# LC_LPF12.net
KiCad netlist of a schematic drawn in Altium Designer
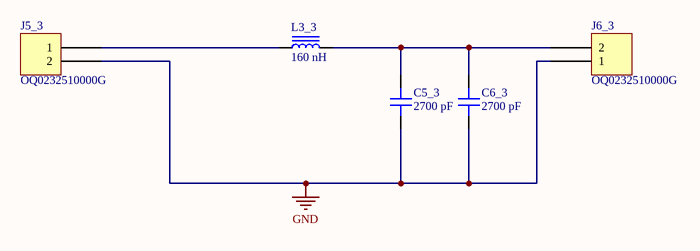
[diagram p0: LC_LPF12.SchDoc]

(export (version "E")
  (design (tool "Eeschema 10.0.6"))
  (components
    (comp (ref "C5_3")
      (value "2700 pF")
      (footprint "CAP 0603_1608")
      (description "CAP CER 2700PF 25V NP0 0603")
      (fields (field (name "PART NUMBER") "C0603C272F3GAC7867") (field (name "MANUFACTURER") "KEMET"))
      (libsource (lib "Celestial Altium Library - altium_library") (part "Capacitor"))
    )
    (comp (ref "C6_3")
      (value "2700 pF")
      (footprint "CAP 0603_1608")
      (description "CAP CER 2700PF 25V NP0 0603")
      (fields (field (name "PART NUMBER") "C0603C272F3GAC7867") (field (name "MANUFACTURER") "KEMET"))
      (libsource (lib "Celestial Altium Library - altium_library") (part "Capacitor"))
    )
    (comp (ref "J5_3")
      (value "OQ0232510000G")
      (footprint "FCI 06-381-2PIN")
      (description "TERM BLOCK HDR 2POS 90DEG 3.81MM")
      (fields (field (name "MANUFACTURER") "Amphenol Anytek"))
      (libsource (lib "Celestial Altium Library - altium_library") (part "2 Pin"))
    )
    (comp (ref "J6_3")
      (value "OQ0232510000G")
      (footprint "FCI 06-381-2PIN")
      (description "TERM BLOCK HDR 2POS 90DEG 3.81MM")
      (fields (field (name "MANUFACTURER") "Amphenol Anytek"))
      (libsource (lib "") (part "2 Pin_1"))
    )
    (comp (ref "L3_3")
      (value "160 nH")
      (footprint "IND 0402_1005 RF WW")
      (description "FIXED IND 160NH 480MA 330MOHM SM")
      (fields
        (field (name "PART NUMBER") "LQW15CNR16J00D")
        (field (name "MANUFACTURER") "Murata Electronics")
      )
      (libsource (lib "Celestial Altium Library - altium_library") (part "Inductor"))
    )
  )
  (nets
    (net (code "1") (name "GND") (class "Default")
      (node (ref "C5_3") (pin "1") (pinfunction "1_1") (pintype "passive"))
      (node (ref "C6_3") (pin "1") (pinfunction "1_1") (pintype "passive"))
      (node (ref "J5_3") (pin "2") (pinfunction "2_2") (pintype "passive"))
      (node (ref "J6_3") (pin "1") (pinfunction "1_1") (pintype "passive"))
    )
    (net (code "2") (name "Net-(C5_3-Pad2)") (class "Default")
      (node (ref "C5_3") (pin "2") (pinfunction "2_2") (pintype "passive"))
      (node (ref "C6_3") (pin "2") (pinfunction "2_2") (pintype "passive"))
      (node (ref "J6_3") (pin "2") (pinfunction "2_2") (pintype "passive"))
      (node (ref "L3_3") (pin "2") (pinfunction "2_2") (pintype "passive"))
    )
    (net (code "3") (name "Net-(J5_3-Pad1)") (class "Default")
      (node (ref "J5_3") (pin "1") (pinfunction "1_1") (pintype "passive"))
      (node (ref "L3_3") (pin "1") (pinfunction "1_1") (pintype "passive"))
    )
  )
)
